# Intar_IR_Module.net
KiCad netlist of a schematic drawn in EAGLE
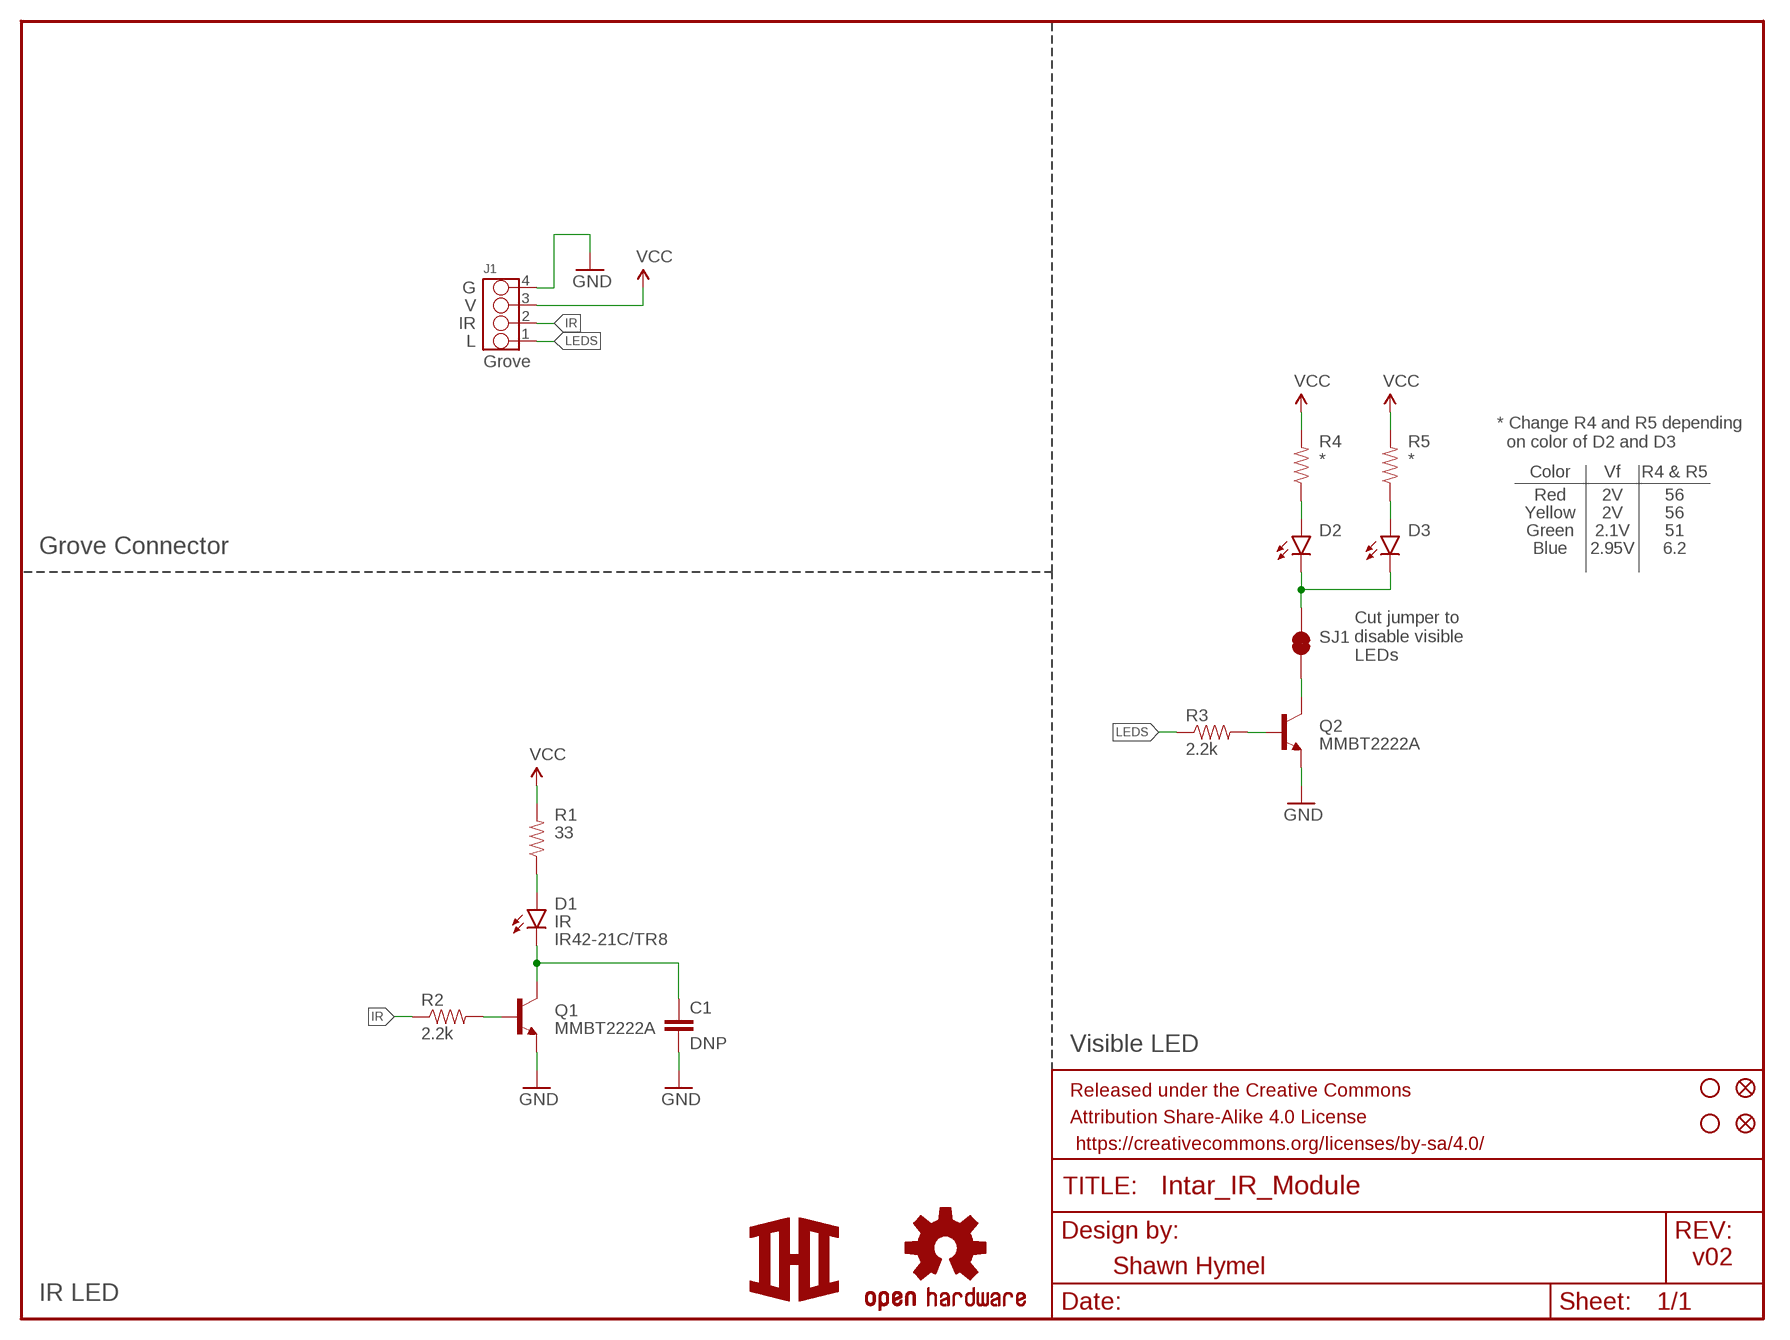
[diagram p0: schematic, sheet 1]

(export (version "E")
  (design (tool "Eeschema 10.0.6"))
  (components
    (comp (ref "C1")
      (value "DNP")
      (footprint "eagle-import:0603-CAP")
      (libsource (lib "eagle-import") (part "10NF/10000PF-50V-10%(0603)"))
    )
    (comp (ref "D1")
      (value "IR")
      (footprint "eagle-import:IR42-21C_TR8")
      (fields (field (name "MFG_NAME") "IR42-21C/TR8"))
      (libsource (lib "eagle-import") (part "LEDIR42-21C/TR8"))
    )
    (comp (ref "D2")
      (value "LED0603")
      (footprint "eagle-import:LED-0603")
      (libsource (lib "eagle-import") (part "LED0603"))
    )
    (comp (ref "D3")
      (value "LED0603")
      (footprint "eagle-import:LED-0603")
      (libsource (lib "eagle-import") (part "LED0603"))
    )
    (comp (ref "FID1")
      (value "FIDUCIAL1X2")
      (footprint "eagle-import:FIDUCIAL-1X2")
      (libsource (lib "eagle-import") (part "FIDUCIAL1X2"))
    )
    (comp (ref "FID2")
      (value "FIDUCIAL1X2")
      (footprint "eagle-import:FIDUCIAL-1X2")
      (libsource (lib "eagle-import") (part "FIDUCIAL1X2"))
    )
    (comp (ref "FRAME1")
      (value "FRAME-LETTER")
      (footprint "eagle-import:CREATIVE_COMMONS")
      (libsource (lib "eagle-import") (part "FRAME-LETTER"))
    )
    (comp (ref "J1")
      (value "GROVE-4P-2.0-3470130P1")
      (footprint "eagle-import:4P-2.0")
      (libsource (lib "eagle-import") (part "GROVE-4P-2.0-3470130P1"))
    )
    (comp (ref "LOGO1")
      (value "OSHW-LOGOS")
      (footprint "eagle-import:OSHW-LOGO-S")
      (libsource (lib "eagle-import") (part "OSHW-LOGOS"))
    )
    (comp (ref "Q1")
      (value "MMBT2222A")
      (footprint "eagle-import:SOT23-3")
      (libsource (lib "eagle-import") (part "TRANSISTOR_NPNMMBT2222A"))
    )
    (comp (ref "Q2")
      (value "MMBT2222A")
      (footprint "eagle-import:SOT23-3")
      (libsource (lib "eagle-import") (part "TRANSISTOR_NPNMMBT2222A"))
    )
    (comp (ref "R1")
      (value "33")
      (footprint "eagle-import:0603-RES")
      (libsource (lib "eagle-import") (part "RESISTOR0603-RES"))
    )
    (comp (ref "R2")
      (value "2.2k")
      (footprint "eagle-import:0603-RES")
      (libsource (lib "eagle-import") (part "2.2KOHM-1/10W-1%(0603)"))
    )
    (comp (ref "R3")
      (value "2.2k")
      (footprint "eagle-import:0603-RES")
      (libsource (lib "eagle-import") (part "2.2KOHM-1/10W-1%(0603)"))
    )
    (comp (ref "R4")
      (value "*")
      (footprint "eagle-import:0603-RES")
      (libsource (lib "eagle-import") (part "RESISTOR0603-RES"))
    )
    (comp (ref "R5")
      (value "*")
      (footprint "eagle-import:0603-RES")
      (libsource (lib "eagle-import") (part "RESISTOR0603-RES"))
    )
    (comp (ref "SJ1")
      (value "JUMPER-PAD-2-NC_BY_TRACE")
      (footprint "eagle-import:PAD-JUMPER-2-NC_BY_TRACE_YES_SILK")
      (libsource (lib "eagle-import") (part "JUMPER-PAD-2-NC_BY_TRACE"))
    )
    (comp (ref "STANDOFF1")
      (value "STAND-OFF")
      (footprint "eagle-import:STAND-OFF")
      (libsource (lib "eagle-import") (part "STAND-OFF"))
    )
    (comp (ref "STANDOFF2")
      (value "STAND-OFF")
      (footprint "eagle-import:STAND-OFF")
      (libsource (lib "eagle-import") (part "STAND-OFF"))
    )
    (comp (ref "U$1")
      (value "LOGOSM")
      (footprint "eagle-import:LOGO_SM")
      (libsource (lib "eagle-import") (part "LOGOSM"))
    )
  )
  (nets
    (net (code "1") (name "GND") (class "Default")
      (node (ref "C1") (pin "2") (pinfunction "2_2") (pintype "passive"))
      (node (ref "J1") (pin "4") (pinfunction "4_4") (pintype "bidirectional"))
      (node (ref "Q1") (pin "2") (pinfunction "E_2") (pintype "passive"))
      (node (ref "Q2") (pin "2") (pinfunction "E_2") (pintype "passive"))
    )
    (net (code "2") (name "IR") (class "Default")
      (node (ref "J1") (pin "2") (pinfunction "2_2") (pintype "bidirectional"))
      (node (ref "R2") (pin "1") (pinfunction "1_1") (pintype "passive"))
    )
    (net (code "3") (name "LEDS") (class "Default")
      (node (ref "J1") (pin "1") (pinfunction "1_1") (pintype "bidirectional"))
      (node (ref "R3") (pin "1") (pinfunction "1_1") (pintype "passive"))
    )
    (net (code "4") (name "Net-(D1-PadA)") (class "Default")
      (node (ref "D1") (pin "A") (pinfunction "A_A") (pintype "passive"))
      (node (ref "R1") (pin "1") (pinfunction "1_1") (pintype "passive"))
    )
    (net (code "5") (name "Net-(D2-PadA)") (class "Default")
      (node (ref "D2") (pin "A") (pinfunction "A_A") (pintype "passive"))
      (node (ref "R4") (pin "1") (pinfunction "1_1") (pintype "passive"))
    )
    (net (code "6") (name "Net-(D2-PadC)") (class "Default")
      (node (ref "D2") (pin "C") (pinfunction "C_C") (pintype "passive"))
      (node (ref "D3") (pin "C") (pinfunction "C_C") (pintype "passive"))
      (node (ref "SJ1") (pin "2") (pinfunction "2_2") (pintype "passive"))
    )
    (net (code "7") (name "Net-(D3-PadA)") (class "Default")
      (node (ref "D3") (pin "A") (pinfunction "A_A") (pintype "passive"))
      (node (ref "R5") (pin "1") (pinfunction "1_1") (pintype "passive"))
    )
    (net (code "8") (name "Net-(Q1-B)") (class "Default")
      (node (ref "Q1") (pin "1") (pinfunction "B_1") (pintype "passive"))
      (node (ref "R2") (pin "2") (pinfunction "2_2") (pintype "passive"))
    )
    (net (code "9") (name "Net-(Q1-C)") (class "Default")
      (node (ref "C1") (pin "1") (pinfunction "1_1") (pintype "passive"))
      (node (ref "D1") (pin "C") (pinfunction "C_C") (pintype "passive"))
      (node (ref "Q1") (pin "3") (pinfunction "C_3") (pintype "passive"))
    )
    (net (code "10") (name "Net-(Q2-B)") (class "Default")
      (node (ref "Q2") (pin "1") (pinfunction "B_1") (pintype "passive"))
      (node (ref "R3") (pin "2") (pinfunction "2_2") (pintype "passive"))
    )
    (net (code "11") (name "Net-(Q2-C)") (class "Default")
      (node (ref "Q2") (pin "3") (pinfunction "C_3") (pintype "passive"))
      (node (ref "SJ1") (pin "1") (pinfunction "1_1") (pintype "passive"))
    )
    (net (code "12") (name "VCC") (class "Default")
      (node (ref "J1") (pin "3") (pinfunction "3_3") (pintype "bidirectional"))
      (node (ref "R1") (pin "2") (pinfunction "2_2") (pintype "passive"))
      (node (ref "R4") (pin "2") (pinfunction "2_2") (pintype "passive"))
      (node (ref "R5") (pin "2") (pinfunction "2_2") (pintype "passive"))
    )
  )
)
